# schema_v5_0.net
KiCad netlist of a schematic drawn in EAGLE
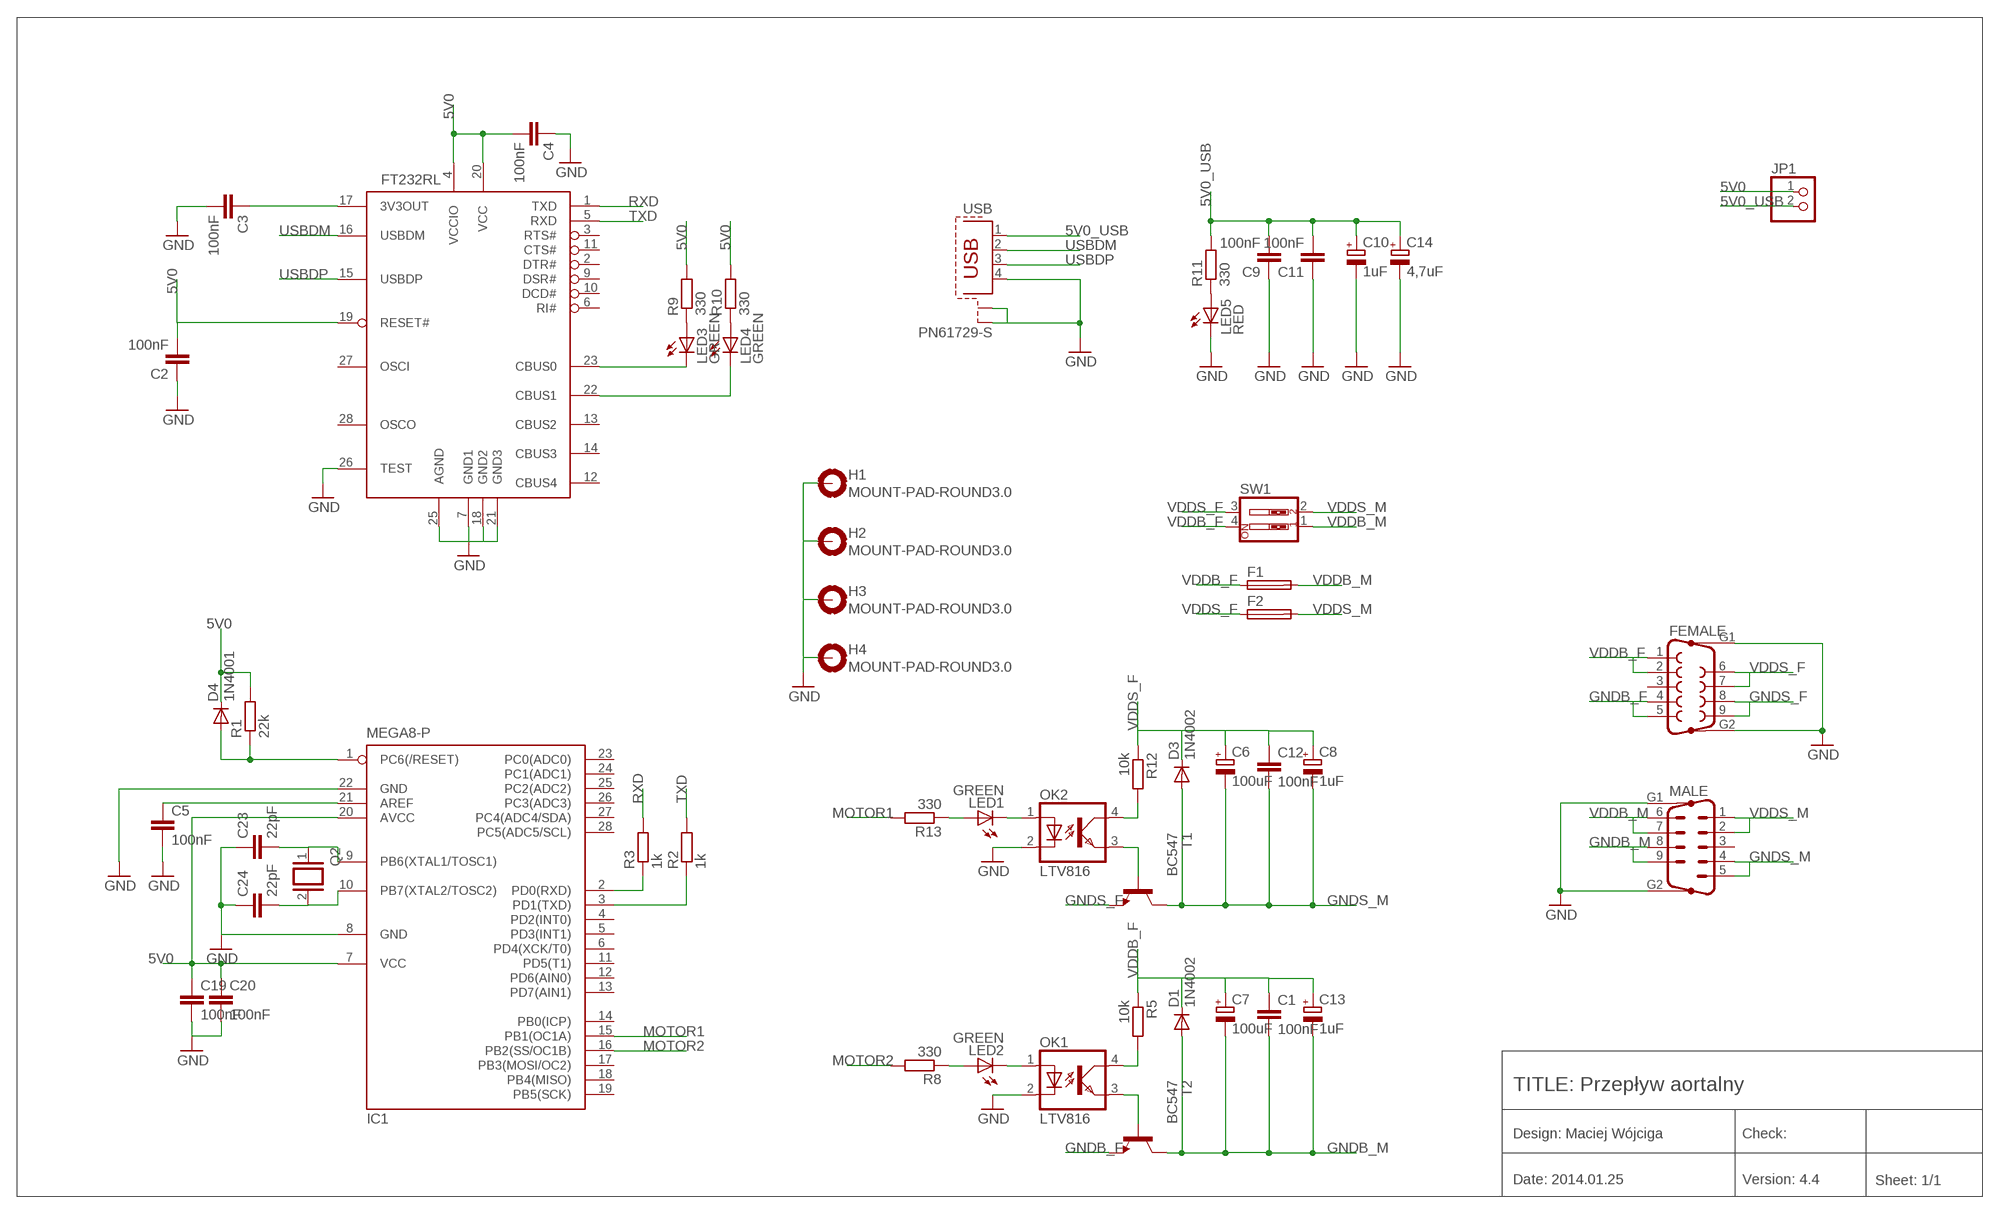
[diagram p0: schematic, sheet 1]

(export (version "E")
  (design (tool "Eeschema 10.0.6"))
  (components
    (comp (ref "C1")
      (value "100nF")
      (footprint "eagle-import:C025-025X050")
      (libsource (lib "eagle-import") (part "C-EU025-025X050"))
    )
    (comp (ref "C2")
      (value "100nF")
      (footprint "eagle-import:C025-025X050")
      (libsource (lib "eagle-import") (part "C-EU025-025X050"))
    )
    (comp (ref "C3")
      (value "100nF")
      (footprint "eagle-import:C025-025X050")
      (libsource (lib "eagle-import") (part "C-EU025-025X050"))
    )
    (comp (ref "C4")
      (value "100nF")
      (footprint "eagle-import:C025-025X050")
      (libsource (lib "eagle-import") (part "C-EU025-025X050"))
    )
    (comp (ref "C5")
      (value "100nF")
      (footprint "eagle-import:C025-025X050")
      (libsource (lib "eagle-import") (part "C-EU025-025X050"))
    )
    (comp (ref "C6")
      (value "100uF")
      (footprint "eagle-import:E5-13")
      (libsource (lib "eagle-import") (part "CPOL-EUE5-13"))
    )
    (comp (ref "C7")
      (value "100uF")
      (footprint "eagle-import:E5-13")
      (libsource (lib "eagle-import") (part "CPOL-EUE5-13"))
    )
    (comp (ref "C8")
      (value "1uF")
      (footprint "eagle-import:E2-4")
      (libsource (lib "eagle-import") (part "CPOL-EUE2-4"))
    )
    (comp (ref "C9")
      (value "100nF")
      (footprint "eagle-import:C025-025X050")
      (libsource (lib "eagle-import") (part "C-EU025-025X050"))
    )
    (comp (ref "C10")
      (value "1uF")
      (footprint "eagle-import:E2,5-5")
      (libsource (lib "eagle-import") (part "CPOL-EUE2.5-5"))
    )
    (comp (ref "C11")
      (value "100nF")
      (footprint "eagle-import:C025-025X050")
      (libsource (lib "eagle-import") (part "C-EU025-025X050"))
    )
    (comp (ref "C12")
      (value "100nF")
      (footprint "eagle-import:C025-025X050")
      (libsource (lib "eagle-import") (part "C-EU025-025X050"))
    )
    (comp (ref "C13")
      (value "1uF")
      (footprint "eagle-import:E2-4")
      (libsource (lib "eagle-import") (part "CPOL-EUE2-4"))
    )
    (comp (ref "C14")
      (value "4,7uF")
      (footprint "eagle-import:E2,5-5")
      (libsource (lib "eagle-import") (part "CPOL-EUE2.5-5"))
    )
    (comp (ref "C19")
      (value "100nF")
      (footprint "eagle-import:C025-025X050")
      (libsource (lib "eagle-import") (part "C-EU025-025X050"))
    )
    (comp (ref "C20")
      (value "100nF")
      (footprint "eagle-import:C025-025X050")
      (libsource (lib "eagle-import") (part "C-EU025-025X050"))
    )
    (comp (ref "C23")
      (value "22pF")
      (footprint "eagle-import:C025-025X050")
      (libsource (lib "eagle-import") (part "C-EU025-025X050"))
    )
    (comp (ref "C24")
      (value "22pF")
      (footprint "eagle-import:C025-025X050")
      (libsource (lib "eagle-import") (part "C-EU025-025X050"))
    )
    (comp (ref "D1")
      (value "1N4002")
      (footprint "eagle-import:DO41-10")
      (libsource (lib "eagle-import") (part "1N4004"))
    )
    (comp (ref "D3")
      (value "1N4002")
      (footprint "eagle-import:DO41-10")
      (libsource (lib "eagle-import") (part "1N4004"))
    )
    (comp (ref "D4")
      (value "1N4001")
      (footprint "eagle-import:DO41-10")
      (libsource (lib "eagle-import") (part "1N4004"))
    )
    (comp (ref "F1")
      (value "GSH15")
      (footprint "eagle-import:GSH15")
      (fields (field (name "MPN") "64900001039"))
      (libsource (lib "eagle-import") (part "GSH15"))
    )
    (comp (ref "F2")
      (value "GSH15")
      (footprint "eagle-import:GSH15")
      (fields (field (name "MPN") "64900001039"))
      (libsource (lib "eagle-import") (part "GSH15"))
    )
    (comp (ref "FEMALE")
      (value "F09HP")
      (footprint "eagle-import:F09HP")
      (libsource (lib "eagle-import") (part "F09HP"))
    )
    (comp (ref "FT232RL")
      (value "FT232RL")
      (footprint "eagle-import:SSOP28DB")
      (libsource (lib "eagle-import") (part "FT232RL"))
    )
    (comp (ref "H1")
      (value "MOUNT-PAD-ROUND3.0")
      (footprint "eagle-import:3,0-PAD")
      (libsource (lib "eagle-import") (part "MOUNT-PAD-ROUND3.0"))
    )
    (comp (ref "H2")
      (value "MOUNT-PAD-ROUND3.0")
      (footprint "eagle-import:3,0-PAD")
      (libsource (lib "eagle-import") (part "MOUNT-PAD-ROUND3.0"))
    )
    (comp (ref "H3")
      (value "MOUNT-PAD-ROUND3.0")
      (footprint "eagle-import:3,0-PAD")
      (libsource (lib "eagle-import") (part "MOUNT-PAD-ROUND3.0"))
    )
    (comp (ref "H4")
      (value "MOUNT-PAD-ROUND3.0")
      (footprint "eagle-import:3,0-PAD")
      (libsource (lib "eagle-import") (part "MOUNT-PAD-ROUND3.0"))
    )
    (comp (ref "IC1")
      (value "MEGA8-P")
      (footprint "eagle-import:DIL28-3")
      (libsource (lib "eagle-import") (part "MEGA8-P"))
    )
    (comp (ref "JP1")
      (value "PINHD-1X2")
      (footprint "eagle-import:1X02")
      (libsource (lib "eagle-import") (part "PINHD-1X2"))
    )
    (comp (ref "LED1")
      (value "GREEN")
      (footprint "eagle-import:LED3MM")
      (libsource (lib "eagle-import") (part "LED3MM"))
    )
    (comp (ref "LED2")
      (value "GREEN")
      (footprint "eagle-import:LED3MM")
      (libsource (lib "eagle-import") (part "LED3MM"))
    )
    (comp (ref "LED3")
      (value "GREEN")
      (footprint "eagle-import:LED3MM")
      (libsource (lib "eagle-import") (part "LED3MM"))
    )
    (comp (ref "LED4")
      (value "GREEN")
      (footprint "eagle-import:LED3MM")
      (libsource (lib "eagle-import") (part "LED3MM"))
    )
    (comp (ref "LED5")
      (value "RED")
      (footprint "eagle-import:LED3MM")
      (libsource (lib "eagle-import") (part "LED3MM"))
    )
    (comp (ref "MALE")
      (value "M09HP")
      (footprint "eagle-import:M09HP")
      (libsource (lib "eagle-import") (part "M09HP"))
    )
    (comp (ref "OK1")
      (value "LTV816")
      (footprint "eagle-import:DIL04")
      (libsource (lib "eagle-import") (part "LTV816"))
    )
    (comp (ref "OK2")
      (value "LTV816")
      (footprint "eagle-import:DIL04")
      (libsource (lib "eagle-import") (part "LTV816"))
    )
    (comp (ref "Q2")
      (value "XTAL/S")
      (footprint "eagle-import:QS")
      (libsource (lib "eagle-import") (part "XTAL/S"))
    )
    (comp (ref "R1")
      (value "22k")
      (footprint "eagle-import:0207_10")
      (libsource (lib "eagle-import") (part "R-EU_0207/10"))
    )
    (comp (ref "R2")
      (value "1k")
      (footprint "eagle-import:0207_10")
      (libsource (lib "eagle-import") (part "R-EU_0207/10"))
    )
    (comp (ref "R3")
      (value "1k")
      (footprint "eagle-import:0207_10")
      (libsource (lib "eagle-import") (part "R-EU_0207/10"))
    )
    (comp (ref "R5")
      (value "10k")
      (footprint "eagle-import:0207_10")
      (libsource (lib "eagle-import") (part "R-EU_0207/10"))
    )
    (comp (ref "R8")
      (value "330")
      (footprint "eagle-import:0207_10")
      (libsource (lib "eagle-import") (part "R-EU_0207/10"))
    )
    (comp (ref "R9")
      (value "330")
      (footprint "eagle-import:0207_10")
      (libsource (lib "eagle-import") (part "R-EU_0207/10"))
    )
    (comp (ref "R10")
      (value "330")
      (footprint "eagle-import:0207_10")
      (libsource (lib "eagle-import") (part "R-EU_0207/10"))
    )
    (comp (ref "R11")
      (value "330")
      (footprint "eagle-import:0207_10")
      (libsource (lib "eagle-import") (part "R-EU_0207/10"))
    )
    (comp (ref "R12")
      (value "10k")
      (footprint "eagle-import:0207_10")
      (libsource (lib "eagle-import") (part "R-EU_0207/10"))
    )
    (comp (ref "R13")
      (value "330")
      (footprint "eagle-import:0207_10")
      (libsource (lib "eagle-import") (part "R-EU_0207/10"))
    )
    (comp (ref "SW1")
      (value "SW_DIP-2")
      (footprint "eagle-import:EDG-02")
      (libsource (lib "eagle-import") (part "SW_DIP-2"))
    )
    (comp (ref "T1")
      (value "BC547")
      (footprint "eagle-import:TO92")
      (libsource (lib "eagle-import") (part "BC547"))
    )
    (comp (ref "T2")
      (value "BC547")
      (footprint "eagle-import:TO92")
      (libsource (lib "eagle-import") (part "BC547"))
    )
    (comp (ref "USB")
      (value "PN61729-S")
      (footprint "eagle-import:PN61729-S")
      (fields (field (name "OC_FARNELL") "unknown") (field (name "OC_NEWARK") "unknown"))
      (libsource (lib "eagle-import") (part "PN61729-S"))
    )
  )
  (nets
    (net (code "1") (name "/5V0") (class "Default")
      (node (ref "C19") (pin "1") (pinfunction "1_1") (pintype "passive"))
      (node (ref "C2") (pin "2") (pinfunction "2_2") (pintype "passive"))
      (node (ref "C20") (pin "1") (pinfunction "1_1") (pintype "passive"))
      (node (ref "C4") (pin "2") (pinfunction "2_2") (pintype "passive"))
      (node (ref "D4") (pin "C") (pinfunction "C_C") (pintype "passive"))
      (node (ref "FT232RL") (pin "19") (pinfunction "RESET#_19") (pintype "input"))
      (node (ref "FT232RL") (pin "20") (pinfunction "VCC_20") (pintype "power_in"))
      (node (ref "FT232RL") (pin "4") (pinfunction "VCCIO_4") (pintype "power_in"))
      (node (ref "IC1") (pin "20") (pinfunction "AVCC_20") (pintype "power_in"))
      (node (ref "IC1") (pin "7") (pinfunction "VCC_7") (pintype "power_in"))
      (node (ref "JP1") (pin "1") (pinfunction "1_1") (pintype "passive"))
      (node (ref "R1") (pin "2") (pinfunction "2_2") (pintype "passive"))
      (node (ref "R10") (pin "2") (pinfunction "2_2") (pintype "passive"))
      (node (ref "R9") (pin "2") (pinfunction "2_2") (pintype "passive"))
    )
    (net (code "2") (name "/5V0_USB") (class "Default")
      (node (ref "C10") (pin "+") (pinfunction "+_+") (pintype "passive"))
      (node (ref "C11") (pin "2") (pinfunction "2_2") (pintype "passive"))
      (node (ref "C14") (pin "+") (pinfunction "+_+") (pintype "passive"))
      (node (ref "C9") (pin "2") (pinfunction "2_2") (pintype "passive"))
      (node (ref "JP1") (pin "2") (pinfunction "2_2") (pintype "passive"))
      (node (ref "R11") (pin "2") (pinfunction "2_2") (pintype "passive"))
      (node (ref "USB") (pin "1") (pinfunction "1_1") (pintype "passive"))
    )
    (net (code "3") (name "/GNDB_F") (class "Default")
      (node (ref "FEMALE") (pin "4") (pinfunction "4_4") (pintype "passive"))
      (node (ref "FEMALE") (pin "5") (pinfunction "5_5") (pintype "passive"))
      (node (ref "T2") (pin "1") (pinfunction "E_1") (pintype "passive"))
    )
    (net (code "4") (name "/GNDB_M") (class "Default")
      (node (ref "C1") (pin "2") (pinfunction "2_2") (pintype "passive"))
      (node (ref "C13") (pin "-") (pinfunction "-_-") (pintype "passive"))
      (node (ref "C7") (pin "-") (pinfunction "-_-") (pintype "passive"))
      (node (ref "D1") (pin "A") (pinfunction "A_A") (pintype "passive"))
      (node (ref "MALE") (pin "8") (pinfunction "8_8") (pintype "passive"))
      (node (ref "MALE") (pin "9") (pinfunction "9_9") (pintype "passive"))
      (node (ref "T2") (pin "3") (pinfunction "C_3") (pintype "passive"))
    )
    (net (code "5") (name "/GNDS_F") (class "Default")
      (node (ref "FEMALE") (pin "8") (pinfunction "8_8") (pintype "passive"))
      (node (ref "FEMALE") (pin "9") (pinfunction "9_9") (pintype "passive"))
      (node (ref "T1") (pin "1") (pinfunction "E_1") (pintype "passive"))
    )
    (net (code "6") (name "/GNDS_M") (class "Default")
      (node (ref "C12") (pin "2") (pinfunction "2_2") (pintype "passive"))
      (node (ref "C6") (pin "-") (pinfunction "-_-") (pintype "passive"))
      (node (ref "C8") (pin "-") (pinfunction "-_-") (pintype "passive"))
      (node (ref "D3") (pin "A") (pinfunction "A_A") (pintype "passive"))
      (node (ref "MALE") (pin "4") (pinfunction "4_4") (pintype "passive"))
      (node (ref "MALE") (pin "5") (pinfunction "5_5") (pintype "passive"))
      (node (ref "T1") (pin "3") (pinfunction "C_3") (pintype "passive"))
    )
    (net (code "7") (name "/MOTOR1") (class "Default")
      (node (ref "IC1") (pin "15") (pinfunction "PB1(OC1A)_15") (pintype "bidirectional"))
      (node (ref "R13") (pin "2") (pinfunction "2_2") (pintype "passive"))
    )
    (net (code "8") (name "/MOTOR2") (class "Default")
      (node (ref "IC1") (pin "16") (pinfunction "PB2(SS/OC1B)_16") (pintype "bidirectional"))
      (node (ref "R8") (pin "2") (pinfunction "2_2") (pintype "passive"))
    )
    (net (code "9") (name "/RXD") (class "Default")
      (node (ref "FT232RL") (pin "1") (pinfunction "TXD_1") (pintype "output"))
      (node (ref "R3") (pin "2") (pinfunction "2_2") (pintype "passive"))
    )
    (net (code "10") (name "/TXD") (class "Default")
      (node (ref "FT232RL") (pin "5") (pinfunction "RXD_5") (pintype "input"))
      (node (ref "R2") (pin "2") (pinfunction "2_2") (pintype "passive"))
    )
    (net (code "11") (name "/USBDM") (class "Default")
      (node (ref "FT232RL") (pin "16") (pinfunction "USBDM_16") (pintype "bidirectional"))
      (node (ref "USB") (pin "2") (pinfunction "2_2") (pintype "passive"))
    )
    (net (code "12") (name "/USBDP") (class "Default")
      (node (ref "FT232RL") (pin "15") (pinfunction "USBDP_15") (pintype "bidirectional"))
      (node (ref "USB") (pin "3") (pinfunction "3_3") (pintype "passive"))
    )
    (net (code "13") (name "/VDDB_F") (class "Default")
      (node (ref "C1") (pin "1") (pinfunction "1_1") (pintype "passive"))
      (node (ref "C13") (pin "+") (pinfunction "+_+") (pintype "passive"))
      (node (ref "C7") (pin "+") (pinfunction "+_+") (pintype "passive"))
      (node (ref "D1") (pin "C") (pinfunction "C_C") (pintype "passive"))
      (node (ref "F1") (pin "1") (pinfunction "1_1") (pintype "passive"))
      (node (ref "FEMALE") (pin "1") (pinfunction "1_1") (pintype "passive"))
      (node (ref "FEMALE") (pin "2") (pinfunction "2_2") (pintype "passive"))
      (node (ref "R5") (pin "1") (pinfunction "1_1") (pintype "passive"))
      (node (ref "SW1") (pin "4") (pinfunction "4_4") (pintype "passive"))
    )
    (net (code "14") (name "/VDDB_M") (class "Default")
      (node (ref "F1") (pin "2") (pinfunction "2_2") (pintype "passive"))
      (node (ref "MALE") (pin "6") (pinfunction "6_6") (pintype "passive"))
      (node (ref "MALE") (pin "7") (pinfunction "7_7") (pintype "passive"))
      (node (ref "SW1") (pin "1") (pinfunction "1_1") (pintype "passive"))
    )
    (net (code "15") (name "/VDDS_F") (class "Default")
      (node (ref "C12") (pin "1") (pinfunction "1_1") (pintype "passive"))
      (node (ref "C6") (pin "+") (pinfunction "+_+") (pintype "passive"))
      (node (ref "C8") (pin "+") (pinfunction "+_+") (pintype "passive"))
      (node (ref "D3") (pin "C") (pinfunction "C_C") (pintype "passive"))
      (node (ref "F2") (pin "1") (pinfunction "1_1") (pintype "passive"))
      (node (ref "FEMALE") (pin "6") (pinfunction "6_6") (pintype "passive"))
      (node (ref "FEMALE") (pin "7") (pinfunction "7_7") (pintype "passive"))
      (node (ref "R12") (pin "1") (pinfunction "1_1") (pintype "passive"))
      (node (ref "SW1") (pin "3") (pinfunction "3_3") (pintype "passive"))
    )
    (net (code "16") (name "/VDDS_M") (class "Default")
      (node (ref "F2") (pin "2") (pinfunction "2_2") (pintype "passive"))
      (node (ref "MALE") (pin "1") (pinfunction "1_1") (pintype "passive"))
      (node (ref "MALE") (pin "2") (pinfunction "2_2") (pintype "passive"))
      (node (ref "SW1") (pin "2") (pinfunction "2_2") (pintype "passive"))
    )
    (net (code "17") (name "GND") (class "Default")
      (node (ref "C10") (pin "-") (pinfunction "-_-") (pintype "passive"))
      (node (ref "C11") (pin "1") (pinfunction "1_1") (pintype "passive"))
      (node (ref "C14") (pin "-") (pinfunction "-_-") (pintype "passive"))
      (node (ref "C19") (pin "2") (pinfunction "2_2") (pintype "passive"))
      (node (ref "C2") (pin "1") (pinfunction "1_1") (pintype "passive"))
      (node (ref "C20") (pin "2") (pinfunction "2_2") (pintype "passive"))
      (node (ref "C23") (pin "1") (pinfunction "1_1") (pintype "passive"))
      (node (ref "C24") (pin "1") (pinfunction "1_1") (pintype "passive"))
      (node (ref "C3") (pin "2") (pinfunction "2_2") (pintype "passive"))
      (node (ref "C4") (pin "1") (pinfunction "1_1") (pintype "passive"))
      (node (ref "C5") (pin "2") (pinfunction "2_2") (pintype "passive"))
      (node (ref "C9") (pin "1") (pinfunction "1_1") (pintype "passive"))
      (node (ref "FEMALE") (pin "G1") (pinfunction "G1_G1") (pintype "passive"))
      (node (ref "FEMALE") (pin "G2") (pinfunction "G2_G2") (pintype "passive"))
      (node (ref "FT232RL") (pin "18") (pinfunction "GND2_18") (pintype "power_in"))
      (node (ref "FT232RL") (pin "21") (pinfunction "GND3_21") (pintype "power_in"))
      (node (ref "FT232RL") (pin "25") (pinfunction "AGND_25") (pintype "power_in"))
      (node (ref "FT232RL") (pin "26") (pinfunction "TEST_26") (pintype "input"))
      (node (ref "FT232RL") (pin "7") (pinfunction "GND1_7") (pintype "power_in"))
      (node (ref "H1") (pin "B3,0") (pinfunction "MOUNT_B3,0") (pintype "passive"))
      (node (ref "H2") (pin "B3,0") (pinfunction "MOUNT_B3,0") (pintype "passive"))
      (node (ref "H3") (pin "B3,0") (pinfunction "MOUNT_B3,0") (pintype "passive"))
      (node (ref "H4") (pin "B3,0") (pinfunction "MOUNT_B3,0") (pintype "passive"))
      (node (ref "IC1") (pin "22") (pinfunction "GND_22") (pintype "power_in"))
      (node (ref "IC1") (pin "8") (pinfunction "GND_8") (pintype "power_in"))
      (node (ref "LED5") (pin "K") (pinfunction "C_K") (pintype "passive"))
      (node (ref "MALE") (pin "G1") (pinfunction "G1_G1") (pintype "passive"))
      (node (ref "MALE") (pin "G2") (pinfunction "G2_G2") (pintype "passive"))
      (node (ref "OK1") (pin "2") (pinfunction "C_2") (pintype "passive"))
      (node (ref "OK2") (pin "2") (pinfunction "C_2") (pintype "passive"))
      (node (ref "USB") (pin "4") (pinfunction "4_4") (pintype "passive"))
      (node (ref "USB") (pin "S1") (pinfunction "S1_S1") (pintype "passive"))
      (node (ref "USB") (pin "S2") (pinfunction "S2_S2") (pintype "passive"))
    )
    (net (code "18") (name "Net-(FT232RL-3V3OUT)") (class "Default")
      (node (ref "C3") (pin "1") (pinfunction "1_1") (pintype "passive"))
      (node (ref "FT232RL") (pin "17") (pinfunction "3V3OUT_17") (pintype "output"))
    )
    (net (code "19") (name "Net-(FT232RL-CBUS0)") (class "Default")
      (node (ref "FT232RL") (pin "23") (pinfunction "CBUS0_23") (pintype "bidirectional"))
      (node (ref "LED3") (pin "K") (pinfunction "C_K") (pintype "passive"))
    )
    (net (code "20") (name "Net-(FT232RL-CBUS1)") (class "Default")
      (node (ref "FT232RL") (pin "22") (pinfunction "CBUS1_22") (pintype "bidirectional"))
      (node (ref "LED4") (pin "K") (pinfunction "C_K") (pintype "passive"))
    )
    (net (code "21") (name "Net-(IC1-AREF)") (class "Default")
      (node (ref "C5") (pin "1") (pinfunction "1_1") (pintype "passive"))
      (node (ref "IC1") (pin "21") (pinfunction "AREF_21") (pintype "passive"))
    )
    (net (code "22") (name "Net-(IC1-PB6(XTAL1{slash}TOSC1))") (class "Default")
      (node (ref "C23") (pin "2") (pinfunction "2_2") (pintype "passive"))
      (node (ref "IC1") (pin "9") (pinfunction "PB6(XTAL1/TOSC1)_9") (pintype "bidirectional"))
      (node (ref "Q2") (pin "1") (pinfunction "1_1") (pintype "passive"))
    )
    (net (code "23") (name "Net-(IC1-PB7(XTAL2{slash}TOSC2))") (class "Default")
      (node (ref "C24") (pin "2") (pinfunction "2_2") (pintype "passive"))
      (node (ref "IC1") (pin "10") (pinfunction "PB7(XTAL2/TOSC2)_10") (pintype "bidirectional"))
      (node (ref "Q2") (pin "2") (pinfunction "2_2") (pintype "passive"))
    )
    (net (code "24") (name "Net-(IC1-PC6({slash}RESET))") (class "Default")
      (node (ref "D4") (pin "A") (pinfunction "A_A") (pintype "passive"))
      (node (ref "IC1") (pin "1") (pinfunction "PC6(/RESET)_1") (pintype "bidirectional"))
      (node (ref "R1") (pin "1") (pinfunction "1_1") (pintype "passive"))
    )
    (net (code "25") (name "Net-(IC1-PD0(RXD))") (class "Default")
      (node (ref "IC1") (pin "2") (pinfunction "PD0(RXD)_2") (pintype "bidirectional"))
      (node (ref "R3") (pin "1") (pinfunction "1_1") (pintype "passive"))
    )
    (net (code "26") (name "Net-(IC1-PD1(TXD))") (class "Default")
      (node (ref "IC1") (pin "3") (pinfunction "PD1(TXD)_3") (pintype "bidirectional"))
      (node (ref "R2") (pin "1") (pinfunction "1_1") (pintype "passive"))
    )
    (net (code "27") (name "Net-(LED1-C)") (class "Default")
      (node (ref "LED1") (pin "K") (pinfunction "C_K") (pintype "passive"))
      (node (ref "OK2") (pin "1") (pinfunction "A_1") (pintype "passive"))
    )
    (net (code "28") (name "Net-(LED1-PadA)") (class "Default")
      (node (ref "LED1") (pin "A") (pinfunction "A_A") (pintype "passive"))
      (node (ref "R13") (pin "1") (pinfunction "1_1") (pintype "passive"))
    )
    (net (code "29") (name "Net-(LED2-C)") (class "Default")
      (node (ref "LED2") (pin "K") (pinfunction "C_K") (pintype "passive"))
      (node (ref "OK1") (pin "1") (pinfunction "A_1") (pintype "passive"))
    )
    (net (code "30") (name "Net-(LED2-PadA)") (class "Default")
      (node (ref "LED2") (pin "A") (pinfunction "A_A") (pintype "passive"))
      (node (ref "R8") (pin "1") (pinfunction "1_1") (pintype "passive"))
    )
    (net (code "31") (name "Net-(LED3-PadA)") (class "Default")
      (node (ref "LED3") (pin "A") (pinfunction "A_A") (pintype "passive"))
      (node (ref "R9") (pin "1") (pinfunction "1_1") (pintype "passive"))
    )
    (net (code "32") (name "Net-(LED4-PadA)") (class "Default")
      (node (ref "LED4") (pin "A") (pinfunction "A_A") (pintype "passive"))
      (node (ref "R10") (pin "1") (pinfunction "1_1") (pintype "passive"))
    )
    (net (code "33") (name "Net-(LED5-PadA)") (class "Default")
      (node (ref "LED5") (pin "A") (pinfunction "A_A") (pintype "passive"))
      (node (ref "R11") (pin "1") (pinfunction "1_1") (pintype "passive"))
    )
    (net (code "34") (name "Net-(OK1-COL)") (class "Default")
      (node (ref "OK1") (pin "4") (pinfunction "COL_4") (pintype "passive"))
      (node (ref "R5") (pin "2") (pinfunction "2_2") (pintype "passive"))
    )
    (net (code "35") (name "Net-(OK1-EMIT)") (class "Default")
      (node (ref "OK1") (pin "3") (pinfunction "EMIT_3") (pintype "passive"))
      (node (ref "T2") (pin "2") (pinfunction "B_2") (pintype "passive"))
    )
    (net (code "36") (name "Net-(OK2-COL)") (class "Default")
      (node (ref "OK2") (pin "4") (pinfunction "COL_4") (pintype "passive"))
      (node (ref "R12") (pin "2") (pinfunction "2_2") (pintype "passive"))
    )
    (net (code "37") (name "Net-(OK2-EMIT)") (class "Default")
      (node (ref "OK2") (pin "3") (pinfunction "EMIT_3") (pintype "passive"))
      (node (ref "T1") (pin "2") (pinfunction "B_2") (pintype "passive"))
    )
    (net (code "38") (name "unconnected-(FEMALE-Pad3)") (class "Default")
      (node (ref "FEMALE") (pin "3") (pinfunction "3_3") (pintype "passive"))
    )
    (net (code "39") (name "unconnected-(FT232RL-CBUS2-Pad13)") (class "Default")
      (node (ref "FT232RL") (pin "13") (pinfunction "CBUS2_13") (pintype "bidirectional"))
    )
    (net (code "40") (name "unconnected-(FT232RL-CBUS3-Pad14)") (class "Default")
      (node (ref "FT232RL") (pin "14") (pinfunction "CBUS3_14") (pintype "bidirectional"))
    )
    (net (code "41") (name "unconnected-(FT232RL-CBUS4-Pad12)") (class "Default")
      (node (ref "FT232RL") (pin "12") (pinfunction "CBUS4_12") (pintype "bidirectional"))
    )
    (net (code "42") (name "unconnected-(FT232RL-CTS#-Pad11)") (class "Default")
      (node (ref "FT232RL") (pin "11") (pinfunction "CTS#_11") (pintype "input"))
    )
    (net (code "43") (name "unconnected-(FT232RL-DCD#-Pad10)") (class "Default")
      (node (ref "FT232RL") (pin "10") (pinfunction "DCD#_10") (pintype "input"))
    )
    (net (code "44") (name "unconnected-(FT232RL-DSR#-Pad9)") (class "Default")
      (node (ref "FT232RL") (pin "9") (pinfunction "DSR#_9") (pintype "input"))
    )
    (net (code "45") (name "unconnected-(FT232RL-DTR#-Pad2)") (class "Default")
      (node (ref "FT232RL") (pin "2") (pinfunction "DTR#_2") (pintype "output"))
    )
    (net (code "46") (name "unconnected-(FT232RL-OSCI-Pad27)") (class "Default")
      (node (ref "FT232RL") (pin "27") (pinfunction "OSCI_27") (pintype "input"))
    )
    (net (code "47") (name "unconnected-(FT232RL-OSCO-Pad28)") (class "Default")
      (node (ref "FT232RL") (pin "28") (pinfunction "OSCO_28") (pintype "output"))
    )
    (net (code "48") (name "unconnected-(FT232RL-RI#-Pad6)") (class "Default")
      (node (ref "FT232RL") (pin "6") (pinfunction "RI#_6") (pintype "input"))
    )
    (net (code "49") (name "unconnected-(FT232RL-RTS#-Pad3)") (class "Default")
      (node (ref "FT232RL") (pin "3") (pinfunction "RTS#_3") (pintype "output"))
    )
    (net (code "50") (name "unconnected-(IC1-PB0(ICP)-Pad14)") (class "Default")
      (node (ref "IC1") (pin "14") (pinfunction "PB0(ICP)_14") (pintype "bidirectional"))
    )
    (net (code "51") (name "unconnected-(IC1-PB3(MOSI{slash}OC2)-Pad17)") (class "Default")
      (node (ref "IC1") (pin "17") (pinfunction "PB3(MOSI/OC2)_17") (pintype "bidirectional"))
    )
    (net (code "52") (name "unconnected-(IC1-PB4(MISO)-Pad18)") (class "Default")
      (node (ref "IC1") (pin "18") (pinfunction "PB4(MISO)_18") (pintype "bidirectional"))
    )
    (net (code "53") (name "unconnected-(IC1-PB5(SCK)-Pad19)") (class "Default")
      (node (ref "IC1") (pin "19") (pinfunction "PB5(SCK)_19") (pintype "bidirectional"))
    )
    (net (code "54") (name "unconnected-(IC1-PC0(ADC0)-Pad23)") (class "Default")
      (node (ref "IC1") (pin "23") (pinfunction "PC0(ADC0)_23") (pintype "bidirectional"))
    )
    (net (code "55") (name "unconnected-(IC1-PC1(ADC1)-Pad24)") (class "Default")
      (node (ref "IC1") (pin "24") (pinfunction "PC1(ADC1)_24") (pintype "bidirectional"))
    )
    (net (code "56") (name "unconnected-(IC1-PC2(ADC2)-Pad25)") (class "Default")
      (node (ref "IC1") (pin "25") (pinfunction "PC2(ADC2)_25") (pintype "bidirectional"))
    )
    (net (code "57") (name "unconnected-(IC1-PC3(ADC3)-Pad26)") (class "Default")
      (node (ref "IC1") (pin "26") (pinfunction "PC3(ADC3)_26") (pintype "bidirectional"))
    )
    (net (code "58") (name "unconnected-(IC1-PC4(ADC4{slash}SDA)-Pad27)") (class "Default")
      (node (ref "IC1") (pin "27") (pinfunction "PC4(ADC4/SDA)_27") (pintype "bidirectional"))
    )
    (net (code "59") (name "unconnected-(IC1-PC5(ADC5{slash}SCL)-Pad28)") (class "Default")
      (node (ref "IC1") (pin "28") (pinfunction "PC5(ADC5/SCL)_28") (pintype "bidirectional"))
    )
    (net (code "60") (name "unconnected-(IC1-PD2(INT0)-Pad4)") (class "Default")
      (node (ref "IC1") (pin "4") (pinfunction "PD2(INT0)_4") (pintype "bidirectional"))
    )
    (net (code "61") (name "unconnected-(IC1-PD3(INT1)-Pad5)") (class "Default")
      (node (ref "IC1") (pin "5") (pinfunction "PD3(INT1)_5") (pintype "bidirectional"))
    )
    (net (code "62") (name "unconnected-(IC1-PD4(XCK{slash}T0)-Pad6)") (class "Default")
      (node (ref "IC1") (pin "6") (pinfunction "PD4(XCK/T0)_6") (pintype "bidirectional"))
    )
    (net (code "63") (name "unconnected-(IC1-PD5(T1)-Pad11)") (class "Default")
      (node (ref "IC1") (pin "11") (pinfunction "PD5(T1)_11") (pintype "bidirectional"))
    )
    (net (code "64") (name "unconnected-(IC1-PD6(AIN0)-Pad12)") (class "Default")
      (node (ref "IC1") (pin "12") (pinfunction "PD6(AIN0)_12") (pintype "bidirectional"))
    )
    (net (code "65") (name "unconnected-(IC1-PD7(AIN1)-Pad13)") (class "Default")
      (node (ref "IC1") (pin "13") (pinfunction "PD7(AIN1)_13") (pintype "bidirectional"))
    )
    (net (code "66") (name "unconnected-(MALE-Pad3)") (class "Default")
      (node (ref "MALE") (pin "3") (pinfunction "3_3") (pintype "passive"))
    )
  )
)
